# MCU.net
KiCad netlist of a schematic drawn in Altium Designer
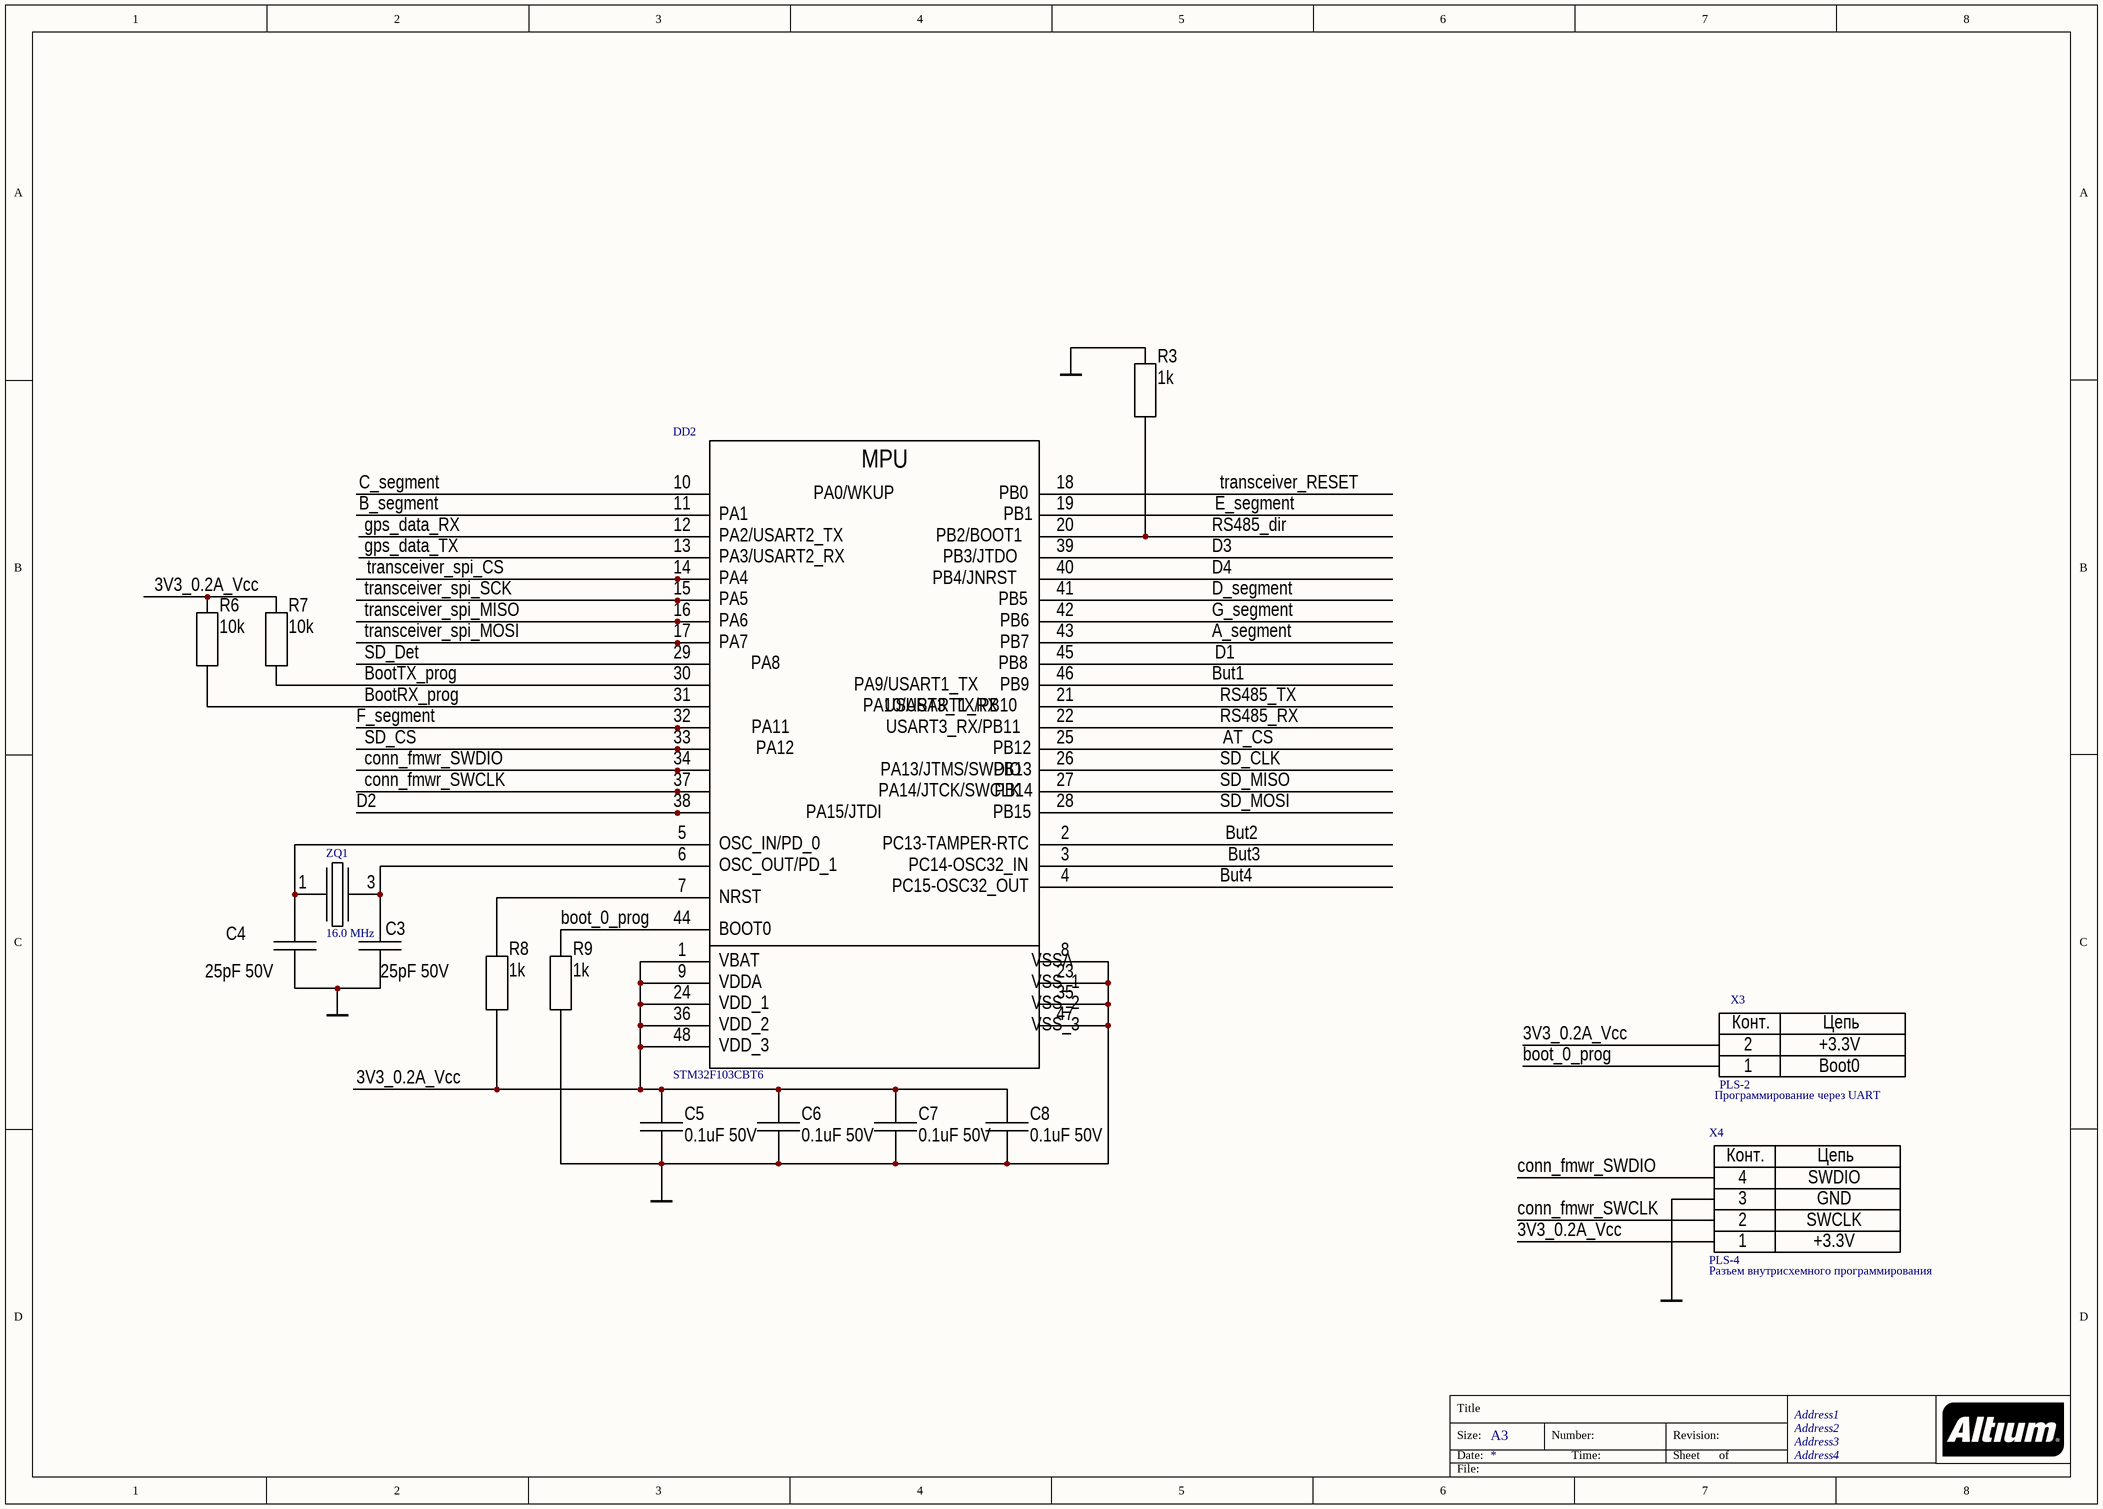
[diagram p0: MCU.SchDoc]

(export (version "E")
  (design (tool "Eeschema 10.0.6"))
  (components
    (comp (ref "C3")
      (value "25pF 50V")
      (footprint "0805_CAP")
      (libsource (lib "Integrated_Library_tikhovikt") (part "Cap_np"))
    )
    (comp (ref "C4")
      (value "25pF 50V")
      (footprint "0805_CAP")
      (libsource (lib "Integrated_Library_tikhovikt") (part "Cap_np"))
    )
    (comp (ref "C5")
      (value "0.1uF 50V")
      (footprint "0805_CAP")
      (libsource (lib "Integrated_Library_tikhovikt") (part "Cap_np"))
    )
    (comp (ref "C6")
      (value "0.1uF 50V")
      (footprint "0805_CAP")
      (libsource (lib "Integrated_Library_tikhovikt") (part "Cap_np"))
    )
    (comp (ref "C7")
      (value "0.1uF 50V")
      (footprint "0805_CAP")
      (libsource (lib "Integrated_Library_tikhovikt") (part "Cap_np"))
    )
    (comp (ref "C8")
      (value "0.1uF 50V")
      (footprint "0805_CAP")
      (libsource (lib "Integrated_Library_tikhovikt") (part "Cap_np"))
    )
    (comp (ref "DD2")
      (value "STM32F103CBT6")
      (footprint "Lqfp-48")
      (libsource (lib "Integrated_Library_tikhovikt") (part "STM32F103-48"))
    )
    (comp (ref "R3")
      (value "1k")
      (footprint "0805_RES")
      (libsource (lib "Integrated_Library_tikhovikt") (part "Res"))
    )
    (comp (ref "R6")
      (value "10k")
      (footprint "0805_RES")
      (libsource (lib "Integrated_Library_tikhovikt") (part "Res"))
    )
    (comp (ref "R7")
      (value "10k")
      (footprint "0805_RES")
      (libsource (lib "Integrated_Library_tikhovikt") (part "Res"))
    )
    (comp (ref "R8")
      (value "1k")
      (footprint "0805_RES")
      (libsource (lib "Integrated_Library_tikhovikt") (part "Res"))
    )
    (comp (ref "R9")
      (value "1k")
      (footprint "0805_RES")
      (libsource (lib "Integrated_Library_tikhovikt") (part "Res"))
    )
    (comp (ref "X3")
      (value "PLS-2")
      (footprint "PLS-2-2.54")
      (fields (field (name "DESTINY") "Программирование через UART"))
      (libsource (lib "Integrated_Library_tikhovikt") (part "2pin_conn"))
    )
    (comp (ref "X4")
      (value "PLS-4")
      (footprint "PLS-4-2.54")
      (fields (field (name "DESTINY") "Разъем внутрисхемного программирования"))
      (libsource (lib "Integrated_Library_tikhovikt") (part "4pin_conn"))
    )
    (comp (ref "ZQ1")
      (value "16.0 MHz")
      (footprint "HC-49")
      (libsource (lib "Integrated_Library_tikhovikt") (part "Cristall"))
    )
  )
  (nets
    (net (code "1") (name "/3V3_0.2A_Vcc") (class "Default")
      (node (ref "C5") (pin "2") (pinfunction "2_2") (pintype "passive"))
      (node (ref "C6") (pin "2") (pinfunction "2_2") (pintype "passive"))
      (node (ref "C7") (pin "2") (pinfunction "2_2") (pintype "passive"))
      (node (ref "C8") (pin "2") (pinfunction "2_2") (pintype "passive"))
      (node (ref "DD2") (pin "1") (pinfunction "1_1") (pintype "passive"))
      (node (ref "DD2") (pin "24") (pinfunction "24_24") (pintype "passive"))
      (node (ref "DD2") (pin "36") (pinfunction "36_36") (pintype "passive"))
      (node (ref "DD2") (pin "48") (pinfunction "48_48") (pintype "passive"))
      (node (ref "DD2") (pin "9") (pinfunction "9_9") (pintype "passive"))
      (node (ref "R6") (pin "2") (pinfunction "2_2") (pintype "passive"))
      (node (ref "R7") (pin "2") (pinfunction "2_2") (pintype "passive"))
      (node (ref "R8") (pin "1") (pinfunction "1_1") (pintype "passive"))
      (node (ref "X3") (pin "2") (pinfunction "2_2") (pintype "passive"))
      (node (ref "X4") (pin "1") (pinfunction "1_1") (pintype "passive"))
    )
    (net (code "2") (name "/AT_CS") (class "Default")
      (node (ref "DD2") (pin "25") (pinfunction "25_25") (pintype "passive"))
    )
    (net (code "3") (name "/A_segment") (class "Default")
      (node (ref "DD2") (pin "43") (pinfunction "43_43") (pintype "passive"))
    )
    (net (code "4") (name "/B_segment") (class "Default")
      (node (ref "DD2") (pin "11") (pinfunction "11_11") (pintype "passive"))
    )
    (net (code "5") (name "/BootRX_prog") (class "Default")
      (node (ref "DD2") (pin "31") (pinfunction "31_31") (pintype "passive"))
      (node (ref "R6") (pin "1") (pinfunction "1_1") (pintype "passive"))
    )
    (net (code "6") (name "/BootTX_prog") (class "Default")
      (node (ref "DD2") (pin "30") (pinfunction "30_30") (pintype "passive"))
      (node (ref "R7") (pin "1") (pinfunction "1_1") (pintype "passive"))
    )
    (net (code "7") (name "/But1") (class "Default")
      (node (ref "DD2") (pin "46") (pinfunction "46_46") (pintype "passive"))
    )
    (net (code "8") (name "/But2") (class "Default")
      (node (ref "DD2") (pin "2") (pinfunction "2_2") (pintype "passive"))
    )
    (net (code "9") (name "/But3") (class "Default")
      (node (ref "DD2") (pin "3") (pinfunction "3_3") (pintype "passive"))
    )
    (net (code "10") (name "/But4") (class "Default")
      (node (ref "DD2") (pin "4") (pinfunction "4_4") (pintype "passive"))
    )
    (net (code "11") (name "/C_segment") (class "Default")
      (node (ref "DD2") (pin "10") (pinfunction "10_10") (pintype "passive"))
    )
    (net (code "12") (name "/D1") (class "Default")
      (node (ref "DD2") (pin "45") (pinfunction "45_45") (pintype "passive"))
    )
    (net (code "13") (name "/D2") (class "Default")
      (node (ref "DD2") (pin "38") (pinfunction "38_38") (pintype "passive"))
    )
    (net (code "14") (name "/D3") (class "Default")
      (node (ref "DD2") (pin "39") (pinfunction "39_39") (pintype "passive"))
    )
    (net (code "15") (name "/D4") (class "Default")
      (node (ref "DD2") (pin "40") (pinfunction "40_40") (pintype "passive"))
    )
    (net (code "16") (name "/D_segment") (class "Default")
      (node (ref "DD2") (pin "41") (pinfunction "41_41") (pintype "passive"))
    )
    (net (code "17") (name "/E_segment") (class "Default")
      (node (ref "DD2") (pin "19") (pinfunction "19_19") (pintype "passive"))
    )
    (net (code "18") (name "/F_segment") (class "Default")
      (node (ref "DD2") (pin "32") (pinfunction "32_32") (pintype "passive"))
    )
    (net (code "19") (name "/G_segment") (class "Default")
      (node (ref "DD2") (pin "42") (pinfunction "42_42") (pintype "passive"))
    )
    (net (code "20") (name "/RS485_RX") (class "Default")
      (node (ref "DD2") (pin "22") (pinfunction "22_22") (pintype "passive"))
    )
    (net (code "21") (name "/RS485_TX") (class "Default")
      (node (ref "DD2") (pin "21") (pinfunction "21_21") (pintype "passive"))
    )
    (net (code "22") (name "/RS485_dir") (class "Default")
      (node (ref "DD2") (pin "20") (pinfunction "20_20") (pintype "passive"))
      (node (ref "R3") (pin "1") (pinfunction "1_1") (pintype "passive"))
    )
    (net (code "23") (name "/SD_CLK") (class "Default")
      (node (ref "DD2") (pin "26") (pinfunction "26_26") (pintype "passive"))
    )
    (net (code "24") (name "/SD_CS") (class "Default")
      (node (ref "DD2") (pin "33") (pinfunction "33_33") (pintype "passive"))
    )
    (net (code "25") (name "/SD_Det") (class "Default")
      (node (ref "DD2") (pin "29") (pinfunction "29_29") (pintype "passive"))
    )
    (net (code "26") (name "/SD_MISO") (class "Default")
      (node (ref "DD2") (pin "27") (pinfunction "27_27") (pintype "passive"))
    )
    (net (code "27") (name "/SD_MOSI") (class "Default")
      (node (ref "DD2") (pin "28") (pinfunction "28_28") (pintype "passive"))
    )
    (net (code "28") (name "/boot_0_prog") (class "Default")
      (node (ref "DD2") (pin "44") (pinfunction "44_44") (pintype "passive"))
      (node (ref "R9") (pin "2") (pinfunction "2_2") (pintype "passive"))
      (node (ref "X3") (pin "1") (pinfunction "1_1") (pintype "passive"))
    )
    (net (code "29") (name "/conn_fmwr_SWCLK") (class "Default")
      (node (ref "DD2") (pin "37") (pinfunction "37_37") (pintype "passive"))
      (node (ref "X4") (pin "2") (pinfunction "2_2") (pintype "passive"))
    )
    (net (code "30") (name "/conn_fmwr_SWDIO") (class "Default")
      (node (ref "DD2") (pin "34") (pinfunction "34_34") (pintype "passive"))
      (node (ref "X4") (pin "4") (pinfunction "4_4") (pintype "passive"))
    )
    (net (code "31") (name "/gps_data_RX") (class "Default")
      (node (ref "DD2") (pin "12") (pinfunction "12_12") (pintype "passive"))
    )
    (net (code "32") (name "/gps_data_TX") (class "Default")
      (node (ref "DD2") (pin "13") (pinfunction "13_13") (pintype "passive"))
    )
    (net (code "33") (name "/transceiver_RESET") (class "Default")
      (node (ref "DD2") (pin "18") (pinfunction "18_18") (pintype "passive"))
    )
    (net (code "34") (name "/transceiver_spi_CS") (class "Default")
      (node (ref "DD2") (pin "14") (pinfunction "14_14") (pintype "passive"))
    )
    (net (code "35") (name "/transceiver_spi_MISO") (class "Default")
      (node (ref "DD2") (pin "16") (pinfunction "16_16") (pintype "passive"))
    )
    (net (code "36") (name "/transceiver_spi_MOSI") (class "Default")
      (node (ref "DD2") (pin "17") (pinfunction "17_17") (pintype "passive"))
    )
    (net (code "37") (name "/transceiver_spi_SCK") (class "Default")
      (node (ref "DD2") (pin "15") (pinfunction "15_15") (pintype "passive"))
    )
    (net (code "38") (name "GND") (class "Default")
      (node (ref "C3") (pin "1") (pinfunction "1_1") (pintype "passive"))
      (node (ref "C4") (pin "1") (pinfunction "1_1") (pintype "passive"))
      (node (ref "C5") (pin "1") (pinfunction "1_1") (pintype "passive"))
      (node (ref "C6") (pin "1") (pinfunction "1_1") (pintype "passive"))
      (node (ref "C7") (pin "1") (pinfunction "1_1") (pintype "passive"))
      (node (ref "C8") (pin "1") (pinfunction "1_1") (pintype "passive"))
      (node (ref "DD2") (pin "23") (pinfunction "23_23") (pintype "passive"))
      (node (ref "DD2") (pin "35") (pinfunction "35_35") (pintype "passive"))
      (node (ref "DD2") (pin "47") (pinfunction "47_47") (pintype "passive"))
      (node (ref "DD2") (pin "8") (pinfunction "8_8") (pintype "passive"))
      (node (ref "R3") (pin "2") (pinfunction "2_2") (pintype "passive"))
      (node (ref "R9") (pin "1") (pinfunction "1_1") (pintype "passive"))
      (node (ref "X4") (pin "3") (pinfunction "3_3") (pintype "passive"))
    )
    (net (code "39") (name "Net-(C3-Pad2)") (class "Default")
      (node (ref "C3") (pin "2") (pinfunction "2_2") (pintype "passive"))
      (node (ref "DD2") (pin "6") (pinfunction "6_6") (pintype "passive"))
      (node (ref "ZQ1") (pin "3") (pinfunction "3_3") (pintype "passive"))
    )
    (net (code "40") (name "Net-(C4-Pad2)") (class "Default")
      (node (ref "C4") (pin "2") (pinfunction "2_2") (pintype "passive"))
      (node (ref "DD2") (pin "5") (pinfunction "5_5") (pintype "passive"))
      (node (ref "ZQ1") (pin "1") (pinfunction "1_1") (pintype "passive"))
    )
    (net (code "41") (name "Net-(DD2-Pad7)") (class "Default")
      (node (ref "DD2") (pin "7") (pinfunction "7_7") (pintype "passive"))
      (node (ref "R8") (pin "2") (pinfunction "2_2") (pintype "passive"))
    )
  )
)
